# HIZ.net
KiCad netlist of a schematic drawn in EAGLE
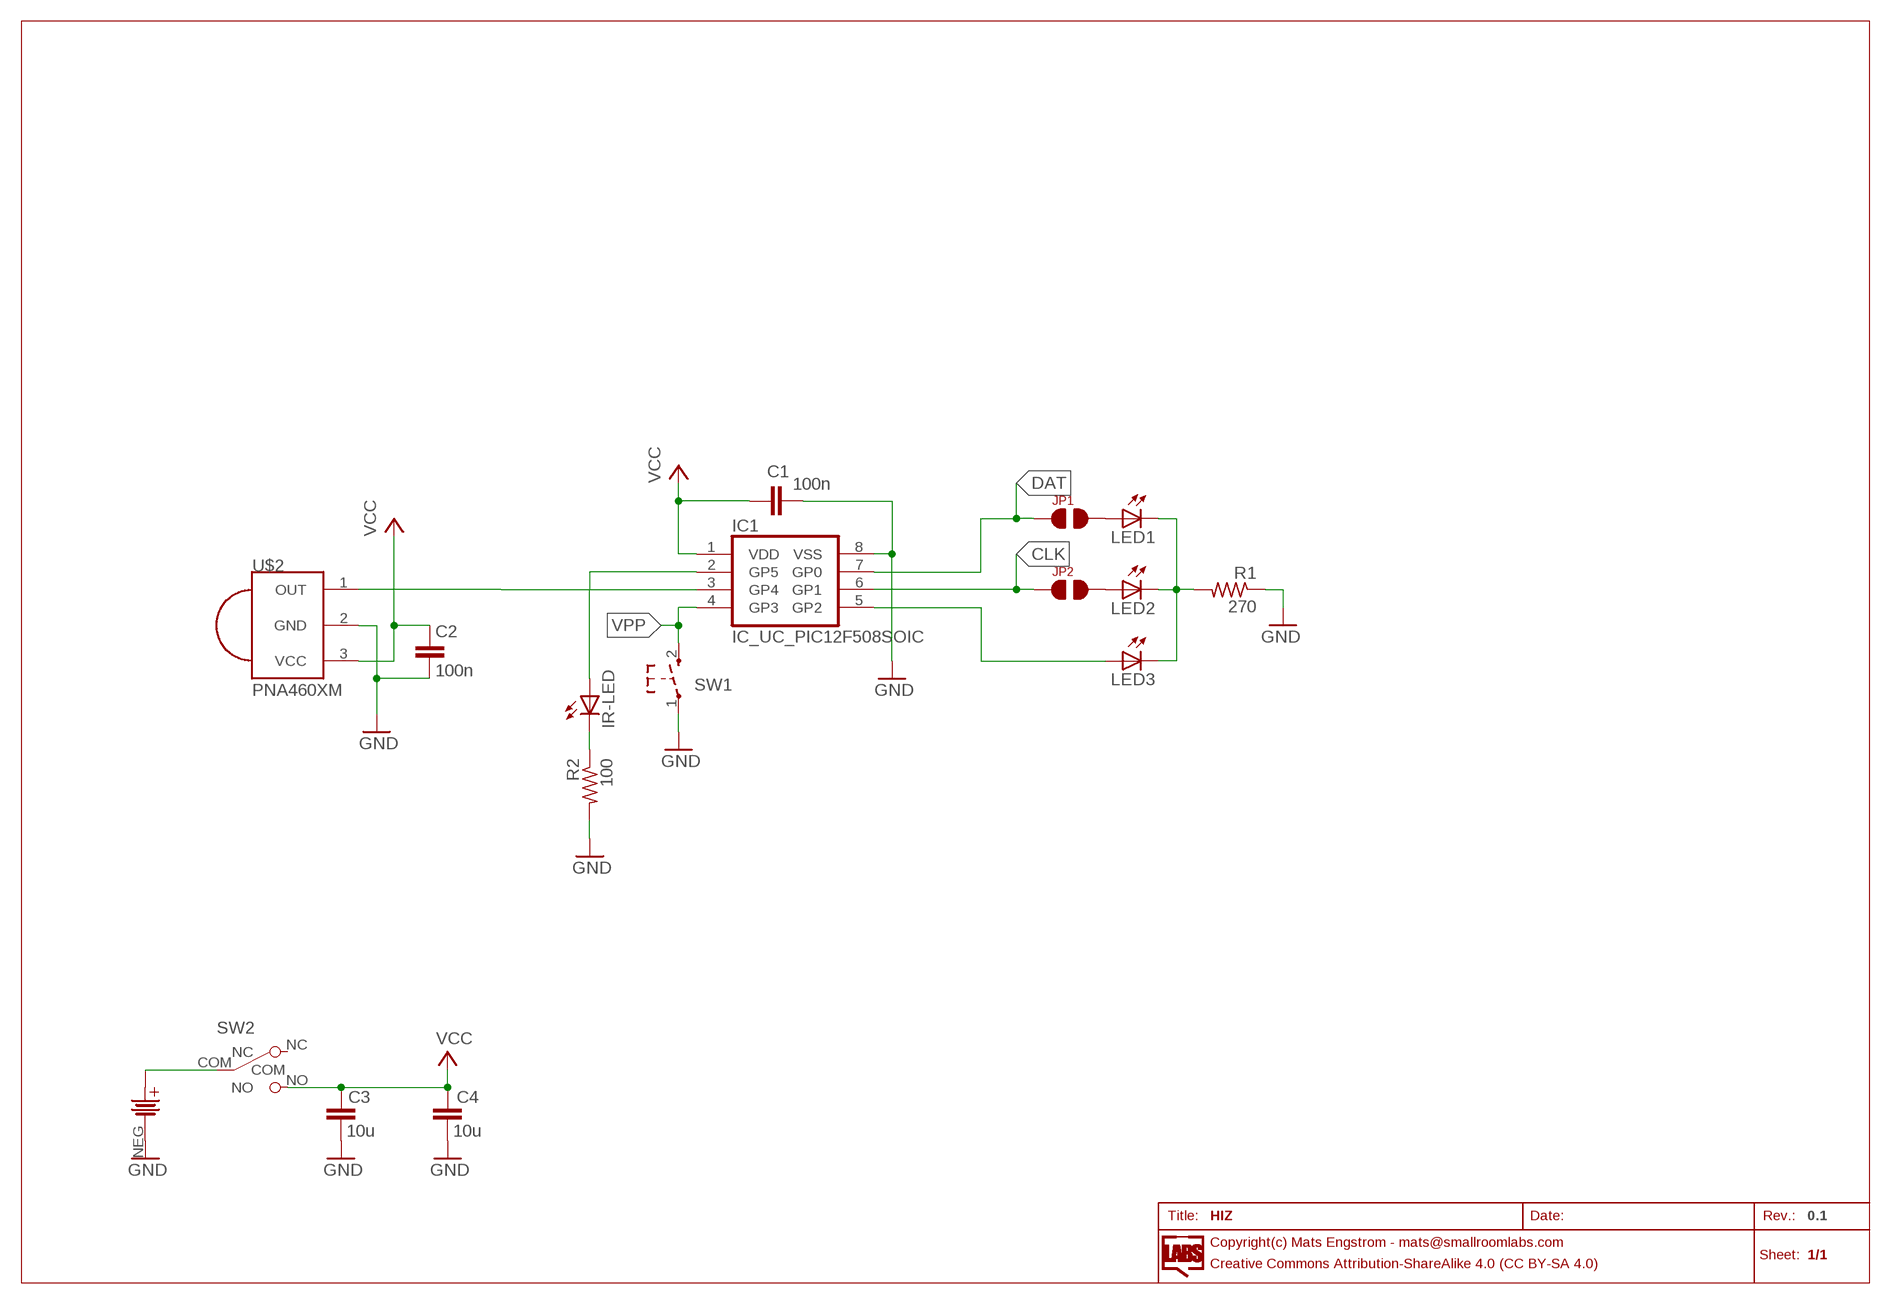
[diagram p0: schematic, sheet 1]

(export (version "E")
  (design (tool "Eeschema 10.0.6"))
  (components
    (comp (ref "BA1")
      (value "BATTERY-3V2032PTH-CHEAP")
      (footprint "eagle-import:CR2032-PTH-CHEAP")
      (libsource (lib "eagle-import") (part "BATTERY-3V2032PTH-CHEAP"))
    )
    (comp (ref "C1")
      (value "100n")
      (footprint "eagle-import:C805")
      (libsource (lib "eagle-import") (part "CAPACITOR_NPOL-0805"))
    )
    (comp (ref "C2")
      (value "100n")
      (footprint "eagle-import:C805")
      (libsource (lib "eagle-import") (part "CAPACITOR_NPOL-0805"))
    )
    (comp (ref "C3")
      (value "10u")
      (footprint "eagle-import:C805")
      (libsource (lib "eagle-import") (part "CAPACITOR_NPOL-0805"))
    )
    (comp (ref "C4")
      (value "10u")
      (footprint "eagle-import:C805")
      (libsource (lib "eagle-import") (part "CAPACITOR_NPOL-0805"))
    )
    (comp (ref "IC1")
      (value "IC_UC_PIC12F508SOIC")
      (footprint "eagle-import:SO-8")
      (libsource (lib "eagle-import") (part "IC_UC_PIC12F508SOIC"))
    )
    (comp (ref "IR-LED")
      (value "LEDSMT1206")
      (footprint "eagle-import:1206")
      (libsource (lib "eagle-import") (part "LEDSMT1206"))
    )
    (comp (ref "JP1")
      (value "JP2-TINY")
      (footprint "eagle-import:JP2-T")
      (libsource (lib "eagle-import") (part "JP2-TINY"))
    )
    (comp (ref "JP2")
      (value "JP2-TINY")
      (footprint "eagle-import:JP2-T")
      (libsource (lib "eagle-import") (part "JP2-TINY"))
    )
    (comp (ref "LED1")
      (value "LED-0805")
      (footprint "eagle-import:LED-805")
      (libsource (lib "eagle-import") (part "LED-0805"))
    )
    (comp (ref "LED2")
      (value "LED-0805")
      (footprint "eagle-import:LED-805")
      (libsource (lib "eagle-import") (part "LED-0805"))
    )
    (comp (ref "LED3")
      (value "LED-0805")
      (footprint "eagle-import:LED-805")
      (libsource (lib "eagle-import") (part "LED-0805"))
    )
    (comp (ref "R1")
      (value "270")
      (footprint "eagle-import:R0805")
      (libsource (lib "eagle-import") (part "R-0805"))
    )
    (comp (ref "R2")
      (value "100")
      (footprint "eagle-import:R0805")
      (libsource (lib "eagle-import") (part "R-0805"))
    )
    (comp (ref "SW1")
      (value "SW_TACT_2P-3X6")
      (footprint "eagle-import:SW_TACT_3X6")
      (libsource (lib "eagle-import") (part "SW_TACT_2P-3X6"))
    )
    (comp (ref "SW2")
      (value "SW_SLIDE")
      (footprint "eagle-import:SLIDE_SWITCH_SMD")
      (libsource (lib "eagle-import") (part "SW_SLIDE"))
    )
    (comp (ref "U$2")
      (value "PNA460XM")
      (footprint "eagle-import:PNA460XM")
      (libsource (lib "eagle-import") (part "PNA460XM"))
    )
  )
  (nets
    (net (code "1") (name "CLK") (class "Default")
      (node (ref "IC1") (pin "6") (pinfunction "GP1_6") (pintype "bidirectional"))
      (node (ref "JP2") (pin "P$1") (pinfunction "P$1_P$1") (pintype "bidirectional"))
    )
    (net (code "2") (name "DAT") (class "Default")
      (node (ref "IC1") (pin "7") (pinfunction "GP0_7") (pintype "bidirectional"))
      (node (ref "JP1") (pin "P$1") (pinfunction "P$1_P$1") (pintype "bidirectional"))
    )
    (net (code "3") (name "GND") (class "Default")
      (node (ref "BA1") (pin "NEG") (pinfunction "MINUS_NEG") (pintype "power_in"))
      (node (ref "C1") (pin "2") (pinfunction "2_2") (pintype "passive"))
      (node (ref "C2") (pin "2") (pinfunction "2_2") (pintype "passive"))
      (node (ref "C3") (pin "2") (pinfunction "2_2") (pintype "passive"))
      (node (ref "C4") (pin "2") (pinfunction "2_2") (pintype "passive"))
      (node (ref "IC1") (pin "8") (pinfunction "VSS_8") (pintype "power_in"))
      (node (ref "R1") (pin "1") (pinfunction "1_1") (pintype "passive"))
      (node (ref "R2") (pin "2") (pinfunction "2_2") (pintype "passive"))
      (node (ref "SW1") (pin "1") (pinfunction "1_1") (pintype "passive"))
      (node (ref "U$2") (pin "2") (pinfunction "GND_2") (pintype "power_in"))
    )
    (net (code "4") (name "Net-(BA1-PLUS-PadPOS@1)") (class "Default")
      (node (ref "BA1") (pin "POS@1") (pinfunction "PLUS_POS@1") (pintype "power_in"))
      (node (ref "BA1") (pin "POS@2") (pinfunction "PLUS_POS@2") (pintype "power_in"))
      (node (ref "BA1") (pin "POS@3") (pinfunction "PLUS_POS@3") (pintype "power_in"))
      (node (ref "BA1") (pin "POS@4") (pinfunction "PLUS_POS@4") (pintype "power_in"))
      (node (ref "SW2") (pin "COM") (pinfunction "COM_COM") (pintype "passive"))
    )
    (net (code "5") (name "Net-(IC1-GP2)") (class "Default")
      (node (ref "IC1") (pin "5") (pinfunction "GP2_5") (pintype "bidirectional"))
      (node (ref "LED3") (pin "A") (pinfunction "A_A") (pintype "passive"))
    )
    (net (code "6") (name "Net-(IC1-GP4)") (class "Default")
      (node (ref "IC1") (pin "3") (pinfunction "GP4_3") (pintype "bidirectional"))
      (node (ref "U$2") (pin "1") (pinfunction "OUT_1") (pintype "output"))
    )
    (net (code "7") (name "Net-(IC1-GP5)") (class "Default")
      (node (ref "IC1") (pin "2") (pinfunction "GP5_2") (pintype "bidirectional"))
      (node (ref "IR-LED") (pin "A") (pinfunction "A_A") (pintype "passive"))
    )
    (net (code "8") (name "Net-(IR-LED-PadC)") (class "Default")
      (node (ref "IR-LED") (pin "C") (pinfunction "C_C") (pintype "passive"))
      (node (ref "R2") (pin "1") (pinfunction "1_1") (pintype "passive"))
    )
    (net (code "9") (name "Net-(JP1-PadP$2)") (class "Default")
      (node (ref "JP1") (pin "P$2") (pinfunction "P$2_P$2") (pintype "bidirectional"))
      (node (ref "LED1") (pin "A") (pinfunction "A_A") (pintype "passive"))
    )
    (net (code "10") (name "Net-(JP2-PadP$2)") (class "Default")
      (node (ref "JP2") (pin "P$2") (pinfunction "P$2_P$2") (pintype "bidirectional"))
      (node (ref "LED2") (pin "A") (pinfunction "A_A") (pintype "passive"))
    )
    (net (code "11") (name "Net-(LED1-PadC)") (class "Default")
      (node (ref "LED1") (pin "C") (pinfunction "C_C") (pintype "passive"))
      (node (ref "LED2") (pin "C") (pinfunction "C_C") (pintype "passive"))
      (node (ref "LED3") (pin "C") (pinfunction "C_C") (pintype "passive"))
      (node (ref "R1") (pin "2") (pinfunction "2_2") (pintype "passive"))
    )
    (net (code "12") (name "VCC") (class "Default")
      (node (ref "C1") (pin "1") (pinfunction "1_1") (pintype "passive"))
      (node (ref "C2") (pin "1") (pinfunction "1_1") (pintype "passive"))
      (node (ref "C3") (pin "1") (pinfunction "1_1") (pintype "passive"))
      (node (ref "C4") (pin "1") (pinfunction "1_1") (pintype "passive"))
      (node (ref "IC1") (pin "1") (pinfunction "VDD_1") (pintype "power_in"))
      (node (ref "SW2") (pin "NO") (pinfunction "NO_NO") (pintype "passive"))
      (node (ref "U$2") (pin "3") (pinfunction "VCC_3") (pintype "power_in"))
    )
    (net (code "13") (name "VPP") (class "Default")
      (node (ref "IC1") (pin "4") (pinfunction "GP3_4") (pintype "bidirectional"))
      (node (ref "SW1") (pin "2") (pinfunction "3_2") (pintype "passive"))
    )
    (net (code "14") (name "unconnected-(SW2-PadNC)") (class "Default")
      (node (ref "SW2") (pin "NC") (pinfunction "NC_NC") (pintype "passive"))
    )
  )
)
